# CAN_MAIN.net
KiCad netlist of a schematic drawn in Altium Designer
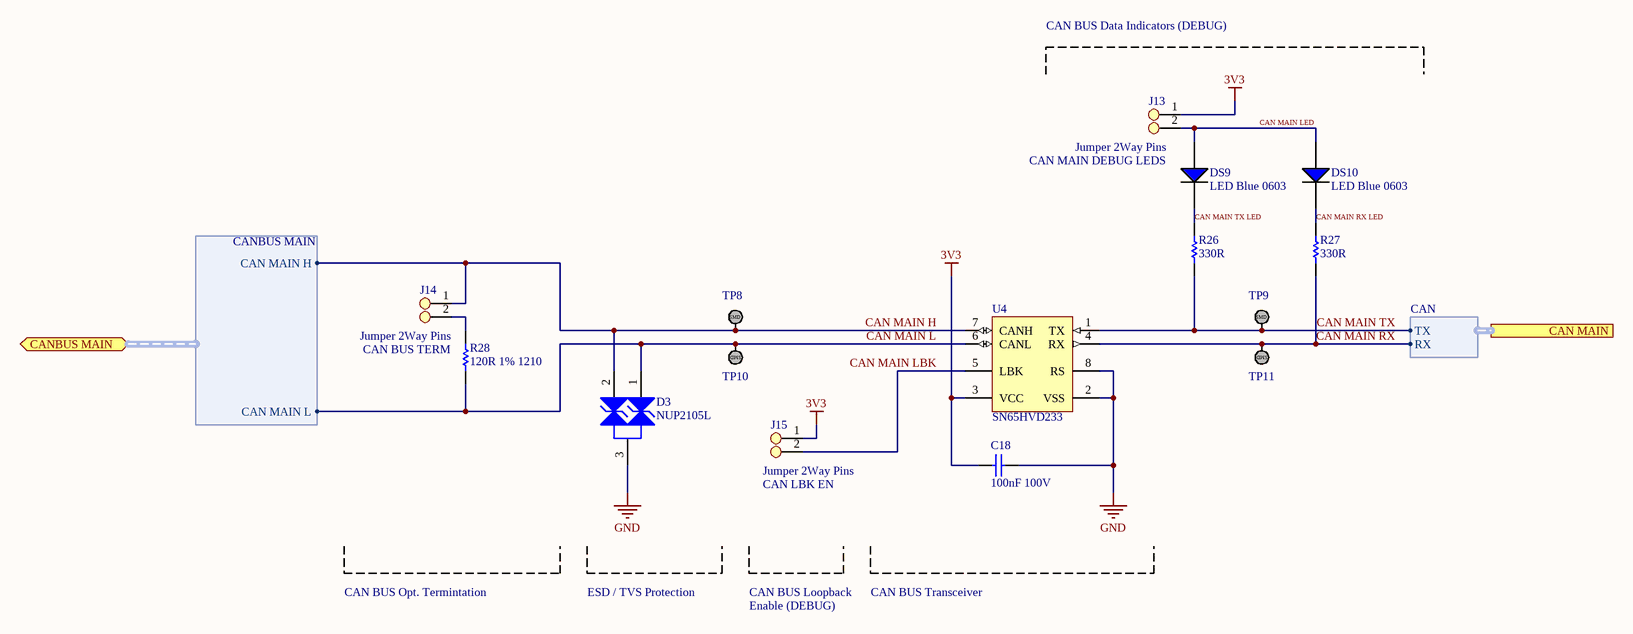
[diagram p0: CAN_MAIN.SchDoc]

(export (version "E")
  (design (tool "Eeschema 10.0.6"))
  (components
    (comp (ref "C18")
      (value "100nF 100V")
      (footprint "Cap_Ceramic_0603")
      (description "Capacitor, Ceramic, SMD, 100nF, 100V, 5%, X7R, 0603")
      (libsource (lib "StandardCapacitors") (part "100nF 100V 5% X7R 0603"))
    )
    (comp (ref "D3")
      (value "NUP2105L")
      (footprint "NUP2105L")
      (libsource (lib "QUTMS_CANLibrary") (part "NUP2105L"))
    )
    (comp (ref "DS9")
      (value "LED Blue 0603")
      (footprint "LED BLUE 0603")
      (libsource (lib "QUTMS_LEDLibrary") (part "LED BLUE 0603"))
    )
    (comp (ref "DS10")
      (value "LED Blue 0603")
      (footprint "LED BLUE 0603")
      (libsource (lib "QUTMS_LEDLibrary") (part "LED BLUE 0603"))
    )
    (comp (ref "J13")
      (value "Jumper 2Way Pins")
      (footprint "Jumper_2Way_Pin")
      (description "Jumper 2Way Side Pins")
      (libsource (lib "QUTMS_JumperLibrary") (part "Jumper 2Way Side Pins"))
    )
    (comp (ref "J14")
      (value "Jumper 2Way Pins")
      (footprint "Jumper_2Way_Pin")
      (description "Jumper 2Way Side Pins")
      (libsource (lib "QUTMS_JumperLibrary") (part "Jumper 2Way Side Pins"))
    )
    (comp (ref "J15")
      (value "Jumper 2Way Pins")
      (footprint "Jumper_2Way_Pin")
      (description "Jumper 2Way Side Pins")
      (libsource (lib "QUTMS_JumperLibrary") (part "Jumper 2Way Side Pins"))
    )
    (comp (ref "R26")
      (value "330R")
      (footprint "Res_ThinFilm_0603")
      (description "Resistor, SMD, 330R, 0.1W, 5%, 0603")
      (libsource (lib "StandardResistors") (part "330R 5% 0603"))
    )
    (comp (ref "R27")
      (value "330R")
      (footprint "Res_ThinFilm_0603")
      (description "Resistor, SMD, 330R, 0.1W, 5%, 0603")
      (libsource (lib "StandardResistors") (part "330R 5% 0603"))
    )
    (comp (ref "R28")
      (value "120R 1% 1210")
      (footprint "Res_ThinFilm_1210")
      (description "Resistor, SMD, 120R, 0.25W, 1%, 1210")
      (libsource (lib "StandardResistors") (part "120R 1% 1210"))
    )
    (comp (ref "TP8")
      (value "TestPoint_SMD")
      (footprint "TestPointSMD")
      (libsource (lib "StandardTest") (part "TestPoint_SMD"))
    )
    (comp (ref "TP9")
      (value "TestPoint_SMD")
      (footprint "TestPointSMD")
      (libsource (lib "StandardTest") (part "TestPoint_SMD"))
    )
    (comp (ref "TP10")
      (value "TestPoint_SMD")
      (footprint "TestPointSMD")
      (libsource (lib "StandardTest") (part "TestPoint_SMD"))
    )
    (comp (ref "TP11")
      (value "TestPoint_SMD")
      (footprint "TestPointSMD")
      (libsource (lib "StandardTest") (part "TestPoint_SMD"))
    )
    (comp (ref "U4")
      (value "SN65HVD233")
      (footprint "SN65HVD233DR")
      (libsource (lib "QUTMS_CANLibrary") (part "SN65HVD233"))
    )
  )
  (nets
    (net (code "4") (name "/CAN MAIN H") (class "Default")
      (node (ref "D3") (pin "2") (pinfunction "2_2") (pintype "passive"))
      (node (ref "J14") (pin "1") (pinfunction "1_1") (pintype "passive"))
      (node (ref "TP8") (pin "1") (pinfunction "1_1") (pintype "passive"))
      (node (ref "U4") (pin "7") (pinfunction "CANH_7") (pintype "bidirectional"))
    )
    (net (code "5") (name "/CAN MAIN L") (class "Default")
      (node (ref "D3") (pin "1") (pinfunction "1_1") (pintype "passive"))
      (node (ref "R28") (pin "1") (pinfunction "1_1") (pintype "passive"))
      (node (ref "TP10") (pin "1") (pinfunction "1_1") (pintype "passive"))
      (node (ref "U4") (pin "6") (pinfunction "CANL_6") (pintype "bidirectional"))
    )
    (net (code "6") (name "/CAN MAIN LBK") (class "Default")
      (node (ref "J15") (pin "2") (pinfunction "2_2") (pintype "passive"))
      (node (ref "U4") (pin "5") (pinfunction "LBK_5") (pintype "passive"))
    )
    (net (code "7") (name "/CAN MAIN LED") (class "Default")
      (node (ref "DS10") (pin "1") (pinfunction "A_1") (pintype "passive"))
      (node (ref "DS9") (pin "1") (pinfunction "A_1") (pintype "passive"))
      (node (ref "J13") (pin "2") (pinfunction "2_2") (pintype "passive"))
    )
    (net (code "8") (name "/CAN MAIN RX") (class "Default")
      (node (ref "R27") (pin "1") (pinfunction "1_1") (pintype "passive"))
      (node (ref "TP11") (pin "1") (pinfunction "1_1") (pintype "passive"))
      (node (ref "U4") (pin "4") (pinfunction "RX_4") (pintype "output"))
    )
    (net (code "9") (name "/CAN MAIN RX LED") (class "Default")
      (node (ref "DS10") (pin "2") (pinfunction "C_2") (pintype "passive"))
      (node (ref "R27") (pin "2") (pinfunction "2_2") (pintype "passive"))
    )
    (net (code "10") (name "/CAN MAIN TX") (class "Default")
      (node (ref "R26") (pin "1") (pinfunction "1_1") (pintype "passive"))
      (node (ref "TP9") (pin "1") (pinfunction "1_1") (pintype "passive"))
      (node (ref "U4") (pin "1") (pinfunction "TX_1") (pintype "input"))
    )
    (net (code "11") (name "/CAN MAIN TX LED") (class "Default")
      (node (ref "DS9") (pin "2") (pinfunction "C_2") (pintype "passive"))
      (node (ref "R26") (pin "2") (pinfunction "2_2") (pintype "passive"))
    )
    (net (code "14") (name "3V3") (class "Default")
      (node (ref "C18") (pin "2") (pinfunction "2_2") (pintype "passive"))
      (node (ref "J13") (pin "1") (pinfunction "1_1") (pintype "passive"))
      (node (ref "J15") (pin "1") (pinfunction "1_1") (pintype "passive"))
      (node (ref "U4") (pin "3") (pinfunction "VCC_3") (pintype "passive"))
    )
    (net (code "15") (name "GND") (class "Default")
      (node (ref "C18") (pin "1") (pinfunction "1_1") (pintype "passive"))
      (node (ref "D3") (pin "3") (pinfunction "3_3") (pintype "passive"))
      (node (ref "U4") (pin "2") (pinfunction "VSS_2") (pintype "passive"))
      (node (ref "U4") (pin "8") (pinfunction "RS_8") (pintype "passive"))
    )
    (net (code "16") (name "Net-(J14-Pad2)") (class "Default")
      (node (ref "J14") (pin "2") (pinfunction "2_2") (pintype "passive"))
      (node (ref "R28") (pin "2") (pinfunction "2_2") (pintype "passive"))
    )
  )
)
